# Frame_Buffer.net
KiCad netlist of a schematic drawn in Altium Designer
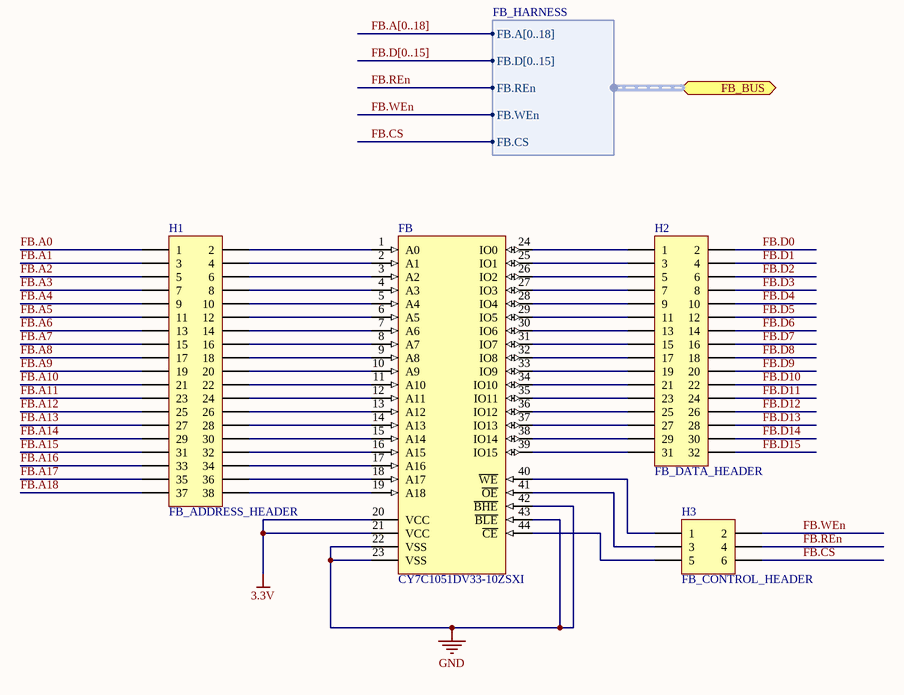
[diagram p0: Frame Buffer.SchDoc]

(export (version "E")
  (design (tool "Eeschema 10.0.6"))
  (components
    (comp (ref "FB")
      (value "CY7C1051DV33-10ZSXI")
      (footprint "TSOP-44-SRAM")
      (libsource (lib "Vector Library") (part "CY7C1051DV33-10ZSXI"))
    )
    (comp (ref "H1")
      (value "FB_ADDRESS_HEADER")
      (footprint "HDR2X19")
      (description "Header, 19-Pin, Dual row")
      (fields (field (name "PUBLISHER") "Altium Limited"))
      (libsource (lib "Miscellaneous Connectors") (part "Header 19X2"))
    )
    (comp (ref "H2")
      (value "FB_DATA_HEADER")
      (footprint "HDR2X16")
      (description "Header, 16-Pin, Dual row")
      (fields (field (name "PUBLISHER") "Altium Limited"))
      (libsource (lib "Miscellaneous Connectors") (part "Header 16X2"))
    )
    (comp (ref "H3")
      (value "FB_CONTROL_HEADER")
      (footprint "HDR2X3")
      (description "Header, 3-Pin, Dual row")
      (fields (field (name "PUBLISHER") "Altium Limited"))
      (libsource (lib "Miscellaneous Connectors") (part "Header 3X2"))
    )
  )
  (nets
    (net (code "2") (name "/FB.A0") (class "Default")
      (node (ref "H1") (pin "1") (pinfunction "1_1") (pintype "passive"))
    )
    (net (code "3") (name "/FB.A1") (class "Default")
      (node (ref "H1") (pin "3") (pinfunction "3_3") (pintype "passive"))
    )
    (net (code "4") (name "/FB.A2") (class "Default")
      (node (ref "H1") (pin "5") (pinfunction "5_5") (pintype "passive"))
    )
    (net (code "5") (name "/FB.A3") (class "Default")
      (node (ref "H1") (pin "7") (pinfunction "7_7") (pintype "passive"))
    )
    (net (code "6") (name "/FB.A4") (class "Default")
      (node (ref "H1") (pin "9") (pinfunction "9_9") (pintype "passive"))
    )
    (net (code "7") (name "/FB.A5") (class "Default")
      (node (ref "H1") (pin "11") (pinfunction "11_11") (pintype "passive"))
    )
    (net (code "8") (name "/FB.A6") (class "Default")
      (node (ref "H1") (pin "13") (pinfunction "13_13") (pintype "passive"))
    )
    (net (code "9") (name "/FB.A7") (class "Default")
      (node (ref "H1") (pin "15") (pinfunction "15_15") (pintype "passive"))
    )
    (net (code "10") (name "/FB.A8") (class "Default")
      (node (ref "H1") (pin "17") (pinfunction "17_17") (pintype "passive"))
    )
    (net (code "11") (name "/FB.A9") (class "Default")
      (node (ref "H1") (pin "19") (pinfunction "19_19") (pintype "passive"))
    )
    (net (code "12") (name "/FB.A10") (class "Default")
      (node (ref "H1") (pin "21") (pinfunction "21_21") (pintype "passive"))
    )
    (net (code "13") (name "/FB.A11") (class "Default")
      (node (ref "H1") (pin "23") (pinfunction "23_23") (pintype "passive"))
    )
    (net (code "14") (name "/FB.A12") (class "Default")
      (node (ref "H1") (pin "25") (pinfunction "25_25") (pintype "passive"))
    )
    (net (code "15") (name "/FB.A13") (class "Default")
      (node (ref "H1") (pin "27") (pinfunction "27_27") (pintype "passive"))
    )
    (net (code "16") (name "/FB.A14") (class "Default")
      (node (ref "H1") (pin "29") (pinfunction "29_29") (pintype "passive"))
    )
    (net (code "17") (name "/FB.A15") (class "Default")
      (node (ref "H1") (pin "31") (pinfunction "31_31") (pintype "passive"))
    )
    (net (code "18") (name "/FB.A16") (class "Default")
      (node (ref "H1") (pin "33") (pinfunction "33_33") (pintype "passive"))
    )
    (net (code "19") (name "/FB.A17") (class "Default")
      (node (ref "H1") (pin "35") (pinfunction "35_35") (pintype "passive"))
    )
    (net (code "20") (name "/FB.A18") (class "Default")
      (node (ref "H1") (pin "37") (pinfunction "37_37") (pintype "passive"))
    )
    (net (code "22") (name "/FB.CS") (class "Default")
      (node (ref "H3") (pin "6") (pinfunction "6_6") (pintype "passive"))
    )
    (net (code "23") (name "/FB.D0") (class "Default")
      (node (ref "H2") (pin "2") (pinfunction "2_2") (pintype "passive"))
    )
    (net (code "24") (name "/FB.D1") (class "Default")
      (node (ref "H2") (pin "4") (pinfunction "4_4") (pintype "passive"))
    )
    (net (code "25") (name "/FB.D2") (class "Default")
      (node (ref "H2") (pin "6") (pinfunction "6_6") (pintype "passive"))
    )
    (net (code "26") (name "/FB.D3") (class "Default")
      (node (ref "H2") (pin "8") (pinfunction "8_8") (pintype "passive"))
    )
    (net (code "27") (name "/FB.D4") (class "Default")
      (node (ref "H2") (pin "10") (pinfunction "10_10") (pintype "passive"))
    )
    (net (code "28") (name "/FB.D5") (class "Default")
      (node (ref "H2") (pin "12") (pinfunction "12_12") (pintype "passive"))
    )
    (net (code "29") (name "/FB.D6") (class "Default")
      (node (ref "H2") (pin "14") (pinfunction "14_14") (pintype "passive"))
    )
    (net (code "30") (name "/FB.D7") (class "Default")
      (node (ref "H2") (pin "16") (pinfunction "16_16") (pintype "passive"))
    )
    (net (code "31") (name "/FB.D8") (class "Default")
      (node (ref "H2") (pin "18") (pinfunction "18_18") (pintype "passive"))
    )
    (net (code "32") (name "/FB.D9") (class "Default")
      (node (ref "H2") (pin "20") (pinfunction "20_20") (pintype "passive"))
    )
    (net (code "33") (name "/FB.D10") (class "Default")
      (node (ref "H2") (pin "22") (pinfunction "22_22") (pintype "passive"))
    )
    (net (code "34") (name "/FB.D11") (class "Default")
      (node (ref "H2") (pin "24") (pinfunction "24_24") (pintype "passive"))
    )
    (net (code "35") (name "/FB.D12") (class "Default")
      (node (ref "H2") (pin "26") (pinfunction "26_26") (pintype "passive"))
    )
    (net (code "36") (name "/FB.D13") (class "Default")
      (node (ref "H2") (pin "28") (pinfunction "28_28") (pintype "passive"))
    )
    (net (code "37") (name "/FB.D14") (class "Default")
      (node (ref "H2") (pin "30") (pinfunction "30_30") (pintype "passive"))
    )
    (net (code "38") (name "/FB.D15") (class "Default")
      (node (ref "H2") (pin "32") (pinfunction "32_32") (pintype "passive"))
    )
    (net (code "40") (name "/FB.REn") (class "Default")
      (node (ref "H3") (pin "4") (pinfunction "4_4") (pintype "passive"))
    )
    (net (code "41") (name "/FB.WEn") (class "Default")
      (node (ref "H3") (pin "2") (pinfunction "2_2") (pintype "passive"))
    )
    (net (code "43") (name "3.3V") (class "Default")
      (node (ref "FB") (pin "20") (pinfunction "VCC_20") (pintype "power_in"))
      (node (ref "FB") (pin "21") (pinfunction "VCC_21") (pintype "power_in"))
    )
    (net (code "44") (name "GND") (class "Default")
      (node (ref "FB") (pin "22") (pinfunction "VSS_22") (pintype "passive"))
      (node (ref "FB") (pin "23") (pinfunction "VSS_23") (pintype "passive"))
      (node (ref "FB") (pin "42") (pinfunction "~{BHE}_42") (pintype "input"))
      (node (ref "FB") (pin "43") (pinfunction "~{BLE}_43") (pintype "input"))
    )
    (net (code "45") (name "Net-(FB-A0)") (class "Default")
      (node (ref "FB") (pin "1") (pinfunction "A0_1") (pintype "input"))
      (node (ref "H1") (pin "2") (pinfunction "2_2") (pintype "passive"))
    )
    (net (code "46") (name "Net-(FB-A1)") (class "Default")
      (node (ref "FB") (pin "2") (pinfunction "A1_2") (pintype "input"))
      (node (ref "H1") (pin "4") (pinfunction "4_4") (pintype "passive"))
    )
    (net (code "47") (name "Net-(FB-A2)") (class "Default")
      (node (ref "FB") (pin "3") (pinfunction "A2_3") (pintype "input"))
      (node (ref "H1") (pin "6") (pinfunction "6_6") (pintype "passive"))
    )
    (net (code "48") (name "Net-(FB-A3)") (class "Default")
      (node (ref "FB") (pin "4") (pinfunction "A3_4") (pintype "input"))
      (node (ref "H1") (pin "8") (pinfunction "8_8") (pintype "passive"))
    )
    (net (code "49") (name "Net-(FB-A4)") (class "Default")
      (node (ref "FB") (pin "5") (pinfunction "A4_5") (pintype "input"))
      (node (ref "H1") (pin "10") (pinfunction "10_10") (pintype "passive"))
    )
    (net (code "50") (name "Net-(FB-A5)") (class "Default")
      (node (ref "FB") (pin "6") (pinfunction "A5_6") (pintype "input"))
      (node (ref "H1") (pin "12") (pinfunction "12_12") (pintype "passive"))
    )
    (net (code "51") (name "Net-(FB-A6)") (class "Default")
      (node (ref "FB") (pin "7") (pinfunction "A6_7") (pintype "input"))
      (node (ref "H1") (pin "14") (pinfunction "14_14") (pintype "passive"))
    )
    (net (code "52") (name "Net-(FB-A7)") (class "Default")
      (node (ref "FB") (pin "8") (pinfunction "A7_8") (pintype "input"))
      (node (ref "H1") (pin "16") (pinfunction "16_16") (pintype "passive"))
    )
    (net (code "53") (name "Net-(FB-A8)") (class "Default")
      (node (ref "FB") (pin "9") (pinfunction "A8_9") (pintype "input"))
      (node (ref "H1") (pin "18") (pinfunction "18_18") (pintype "passive"))
    )
    (net (code "54") (name "Net-(FB-A9)") (class "Default")
      (node (ref "FB") (pin "10") (pinfunction "A9_10") (pintype "input"))
      (node (ref "H1") (pin "20") (pinfunction "20_20") (pintype "passive"))
    )
    (net (code "55") (name "Net-(FB-A10)") (class "Default")
      (node (ref "FB") (pin "11") (pinfunction "A10_11") (pintype "input"))
      (node (ref "H1") (pin "22") (pinfunction "22_22") (pintype "passive"))
    )
    (net (code "56") (name "Net-(FB-A11)") (class "Default")
      (node (ref "FB") (pin "12") (pinfunction "A11_12") (pintype "input"))
      (node (ref "H1") (pin "24") (pinfunction "24_24") (pintype "passive"))
    )
    (net (code "57") (name "Net-(FB-A12)") (class "Default")
      (node (ref "FB") (pin "13") (pinfunction "A12_13") (pintype "input"))
      (node (ref "H1") (pin "26") (pinfunction "26_26") (pintype "passive"))
    )
    (net (code "58") (name "Net-(FB-A13)") (class "Default")
      (node (ref "FB") (pin "14") (pinfunction "A13_14") (pintype "input"))
      (node (ref "H1") (pin "28") (pinfunction "28_28") (pintype "passive"))
    )
    (net (code "59") (name "Net-(FB-A14)") (class "Default")
      (node (ref "FB") (pin "15") (pinfunction "A14_15") (pintype "input"))
      (node (ref "H1") (pin "30") (pinfunction "30_30") (pintype "passive"))
    )
    (net (code "60") (name "Net-(FB-A15)") (class "Default")
      (node (ref "FB") (pin "16") (pinfunction "A15_16") (pintype "input"))
      (node (ref "H1") (pin "32") (pinfunction "32_32") (pintype "passive"))
    )
    (net (code "61") (name "Net-(FB-A16)") (class "Default")
      (node (ref "FB") (pin "17") (pinfunction "A16_17") (pintype "input"))
      (node (ref "H1") (pin "34") (pinfunction "34_34") (pintype "passive"))
    )
    (net (code "62") (name "Net-(FB-A17)") (class "Default")
      (node (ref "FB") (pin "18") (pinfunction "A17_18") (pintype "input"))
      (node (ref "H1") (pin "36") (pinfunction "36_36") (pintype "passive"))
    )
    (net (code "63") (name "Net-(FB-A18)") (class "Default")
      (node (ref "FB") (pin "19") (pinfunction "A18_19") (pintype "input"))
      (node (ref "H1") (pin "38") (pinfunction "38_38") (pintype "passive"))
    )
    (net (code "64") (name "Net-(FB-IO0)") (class "Default")
      (node (ref "FB") (pin "24") (pinfunction "IO0_24") (pintype "bidirectional"))
      (node (ref "H2") (pin "1") (pinfunction "1_1") (pintype "passive"))
    )
    (net (code "65") (name "Net-(FB-IO1)") (class "Default")
      (node (ref "FB") (pin "25") (pinfunction "IO1_25") (pintype "bidirectional"))
      (node (ref "H2") (pin "3") (pinfunction "3_3") (pintype "passive"))
    )
    (net (code "66") (name "Net-(FB-IO2)") (class "Default")
      (node (ref "FB") (pin "26") (pinfunction "IO2_26") (pintype "bidirectional"))
      (node (ref "H2") (pin "5") (pinfunction "5_5") (pintype "passive"))
    )
    (net (code "67") (name "Net-(FB-IO3)") (class "Default")
      (node (ref "FB") (pin "27") (pinfunction "IO3_27") (pintype "bidirectional"))
      (node (ref "H2") (pin "7") (pinfunction "7_7") (pintype "passive"))
    )
    (net (code "68") (name "Net-(FB-IO4)") (class "Default")
      (node (ref "FB") (pin "28") (pinfunction "IO4_28") (pintype "bidirectional"))
      (node (ref "H2") (pin "9") (pinfunction "9_9") (pintype "passive"))
    )
    (net (code "69") (name "Net-(FB-IO5)") (class "Default")
      (node (ref "FB") (pin "29") (pinfunction "IO5_29") (pintype "bidirectional"))
      (node (ref "H2") (pin "11") (pinfunction "11_11") (pintype "passive"))
    )
    (net (code "70") (name "Net-(FB-IO6)") (class "Default")
      (node (ref "FB") (pin "30") (pinfunction "IO6_30") (pintype "bidirectional"))
      (node (ref "H2") (pin "13") (pinfunction "13_13") (pintype "passive"))
    )
    (net (code "71") (name "Net-(FB-IO7)") (class "Default")
      (node (ref "FB") (pin "31") (pinfunction "IO7_31") (pintype "bidirectional"))
      (node (ref "H2") (pin "15") (pinfunction "15_15") (pintype "passive"))
    )
    (net (code "72") (name "Net-(FB-IO8)") (class "Default")
      (node (ref "FB") (pin "32") (pinfunction "IO8_32") (pintype "bidirectional"))
      (node (ref "H2") (pin "17") (pinfunction "17_17") (pintype "passive"))
    )
    (net (code "73") (name "Net-(FB-IO9)") (class "Default")
      (node (ref "FB") (pin "33") (pinfunction "IO9_33") (pintype "bidirectional"))
      (node (ref "H2") (pin "19") (pinfunction "19_19") (pintype "passive"))
    )
    (net (code "74") (name "Net-(FB-IO10)") (class "Default")
      (node (ref "FB") (pin "34") (pinfunction "IO10_34") (pintype "bidirectional"))
      (node (ref "H2") (pin "21") (pinfunction "21_21") (pintype "passive"))
    )
    (net (code "75") (name "Net-(FB-IO11)") (class "Default")
      (node (ref "FB") (pin "35") (pinfunction "IO11_35") (pintype "bidirectional"))
      (node (ref "H2") (pin "23") (pinfunction "23_23") (pintype "passive"))
    )
    (net (code "76") (name "Net-(FB-IO12)") (class "Default")
      (node (ref "FB") (pin "36") (pinfunction "IO12_36") (pintype "bidirectional"))
      (node (ref "H2") (pin "25") (pinfunction "25_25") (pintype "passive"))
    )
    (net (code "77") (name "Net-(FB-IO13)") (class "Default")
      (node (ref "FB") (pin "37") (pinfunction "IO13_37") (pintype "bidirectional"))
      (node (ref "H2") (pin "27") (pinfunction "27_27") (pintype "passive"))
    )
    (net (code "78") (name "Net-(FB-IO14)") (class "Default")
      (node (ref "FB") (pin "38") (pinfunction "IO14_38") (pintype "bidirectional"))
      (node (ref "H2") (pin "29") (pinfunction "29_29") (pintype "passive"))
    )
    (net (code "79") (name "Net-(FB-IO15)") (class "Default")
      (node (ref "FB") (pin "39") (pinfunction "IO15_39") (pintype "bidirectional"))
      (node (ref "H2") (pin "31") (pinfunction "31_31") (pintype "passive"))
    )
    (net (code "80") (name "Net-(FB-~{CE})") (class "Default")
      (node (ref "FB") (pin "44") (pinfunction "~{CE}_44") (pintype "input"))
      (node (ref "H3") (pin "5") (pinfunction "5_5") (pintype "passive"))
    )
    (net (code "81") (name "Net-(FB-~{OE})") (class "Default")
      (node (ref "FB") (pin "41") (pinfunction "~{OE}_41") (pintype "input"))
      (node (ref "H3") (pin "3") (pinfunction "3_3") (pintype "passive"))
    )
    (net (code "82") (name "Net-(FB-~{WE})") (class "Default")
      (node (ref "FB") (pin "40") (pinfunction "~{WE}_40") (pintype "input"))
      (node (ref "H3") (pin "1") (pinfunction "1_1") (pintype "passive"))
    )
  )
)
